# CrackberryPi_1_0_6_2_random.net
KiCad netlist of a schematic drawn in EAGLE
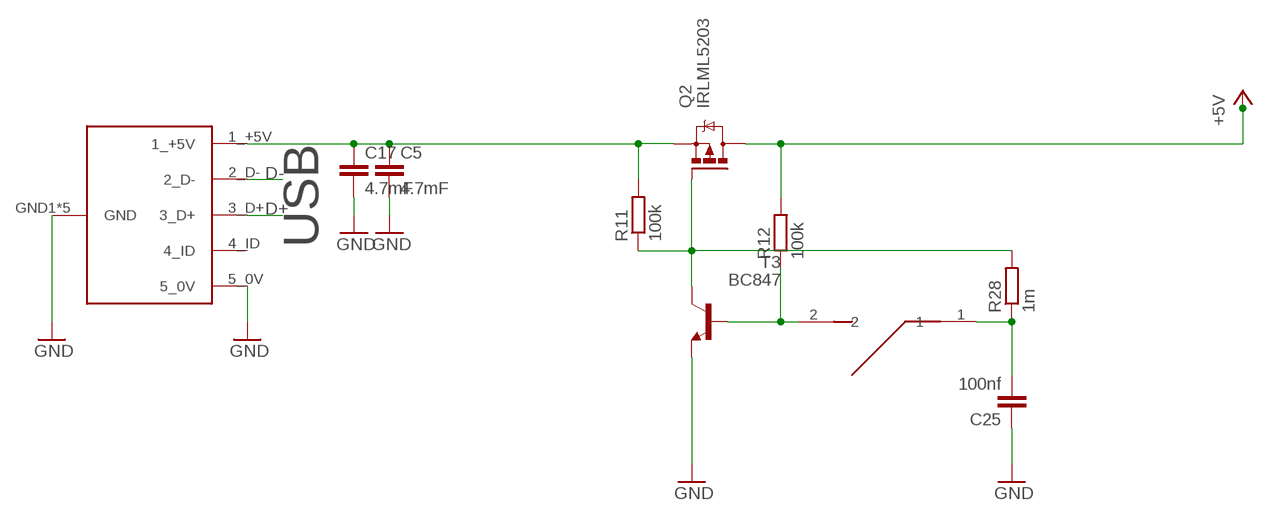
[diagram p0: schematic, sheet 1, part 1 of 2]
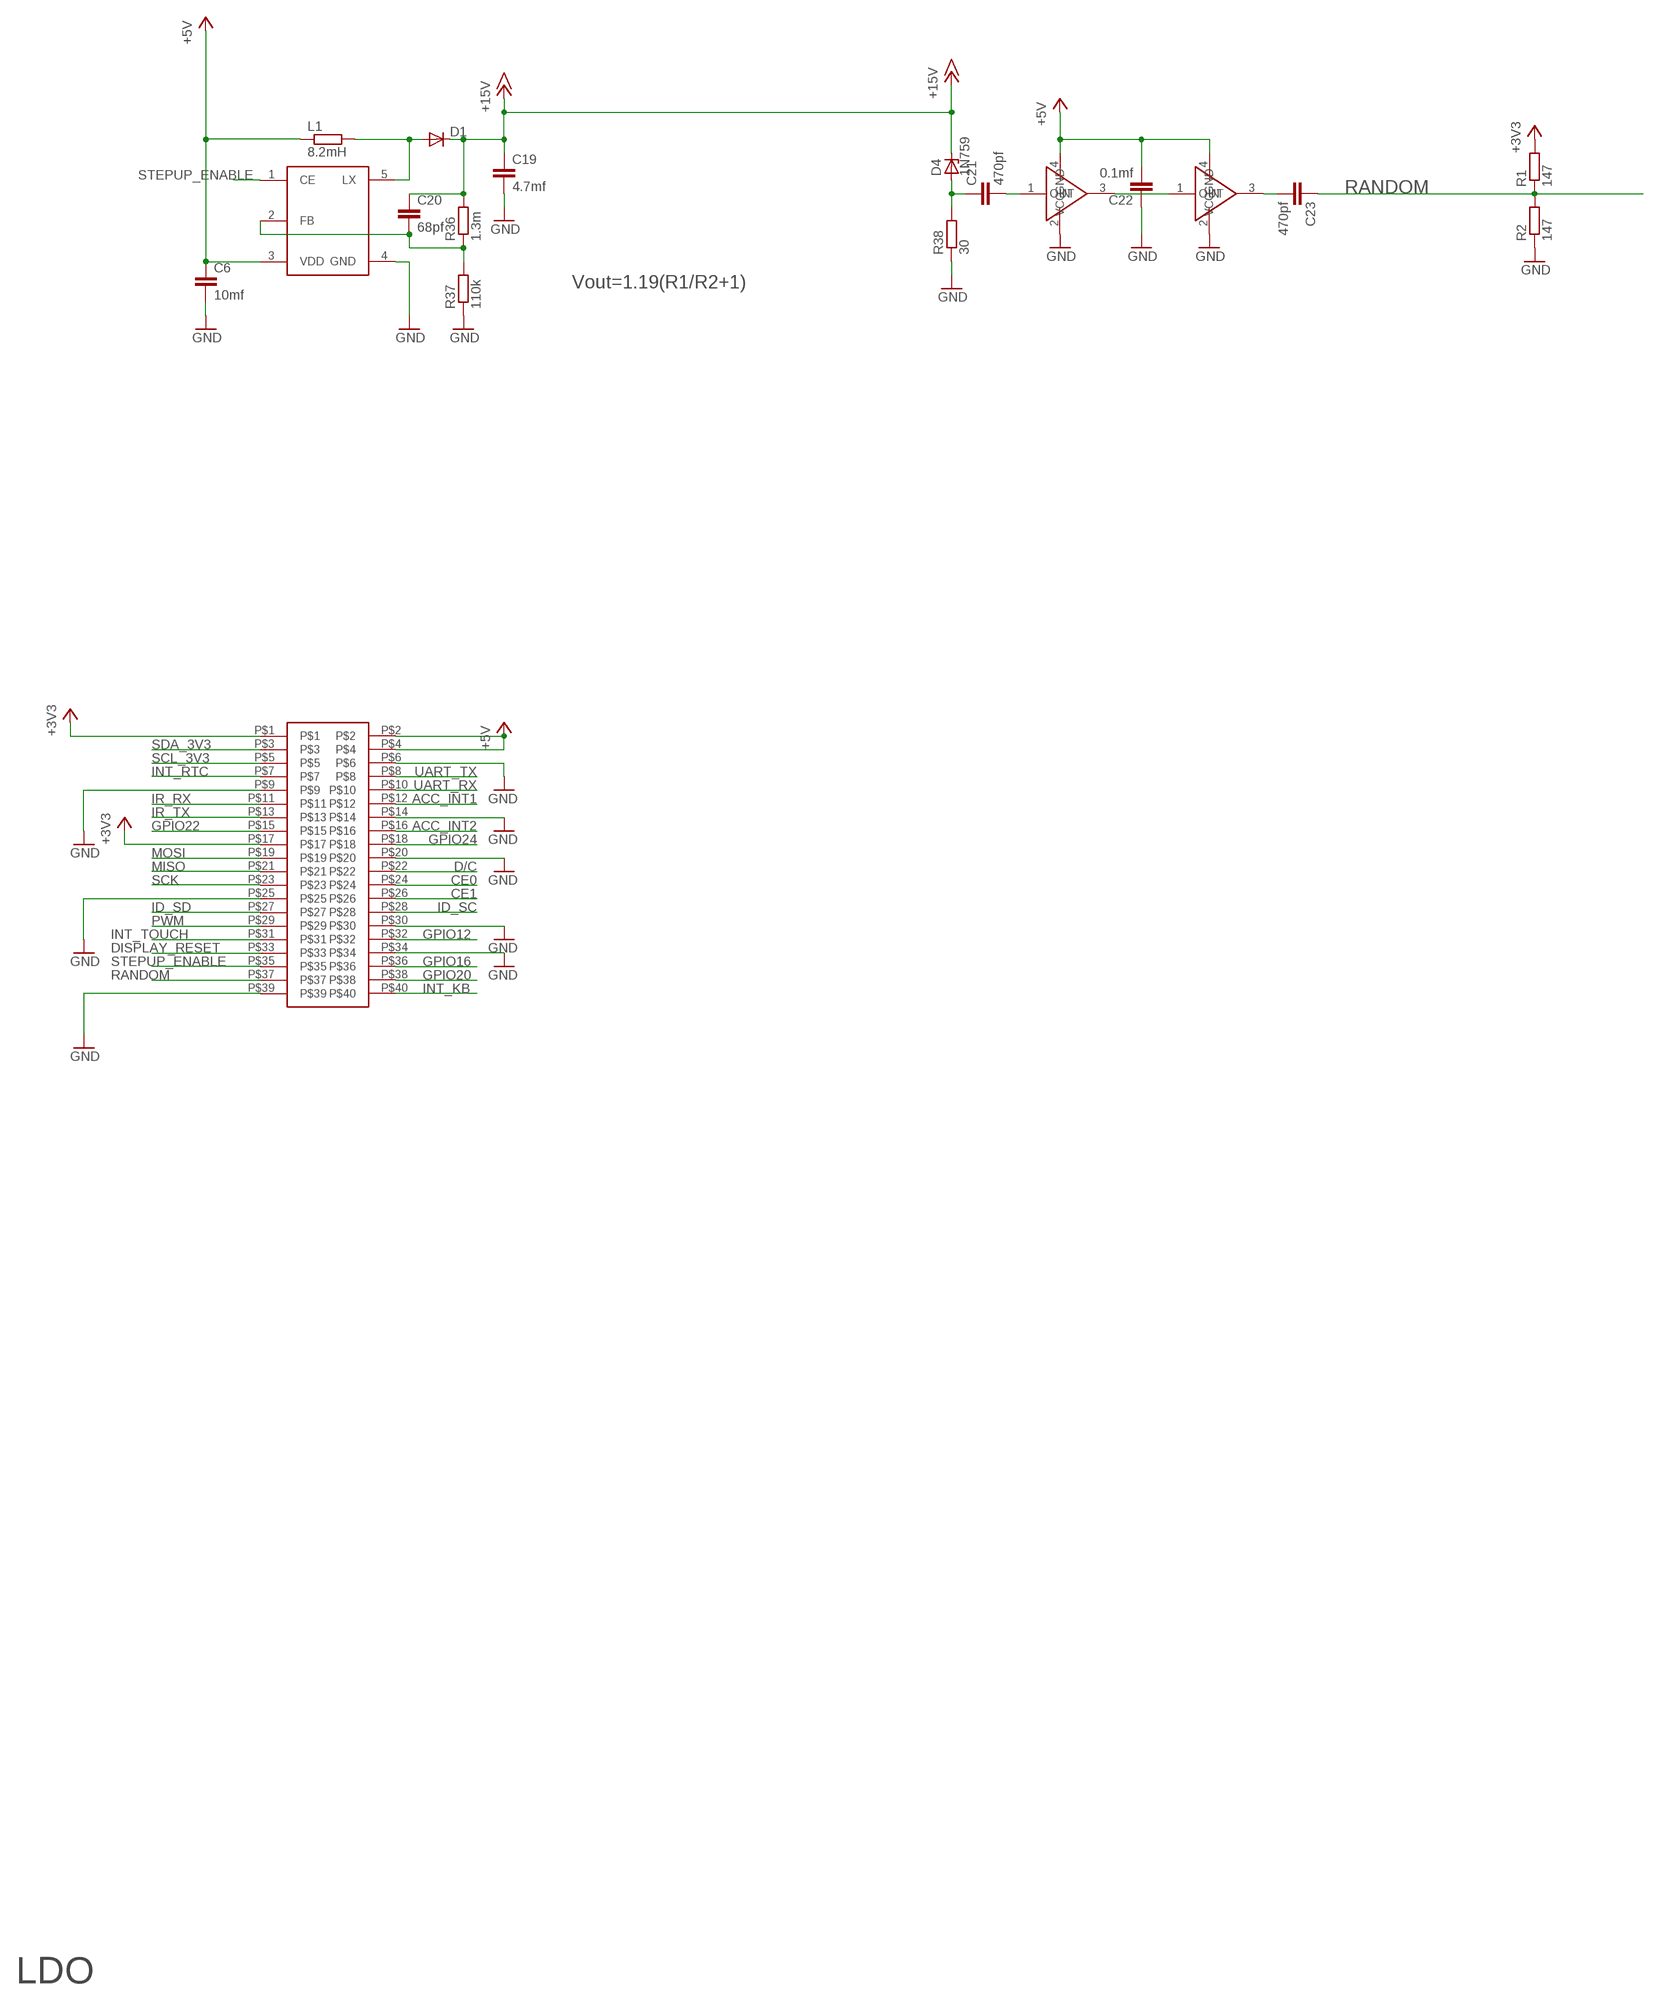
[diagram p1: schematic, sheet 1, part 2 of 2]

(export (version "E")
  (design (tool "Eeschema 10.0.6"))
  (components
    (comp (ref "C5")
      (value "4.7mF")
      (footprint "eagle-import:C0603")
      (libsource (lib "eagle-import") (part "C-EUC0603"))
    )
    (comp (ref "C6")
      (value "10mf")
      (footprint "eagle-import:C0603")
      (libsource (lib "eagle-import") (part "C-EUC0603"))
    )
    (comp (ref "C17")
      (value "4.7mF")
      (footprint "eagle-import:C0603")
      (libsource (lib "eagle-import") (part "C-EUC0603"))
    )
    (comp (ref "C19")
      (value "4.7mf")
      (footprint "eagle-import:C0603")
      (libsource (lib "eagle-import") (part "C-EUC0603"))
    )
    (comp (ref "C20")
      (value "68pf")
      (footprint "eagle-import:C0603")
      (libsource (lib "eagle-import") (part "C-EUC0603"))
    )
    (comp (ref "C21")
      (value "470pf")
      (footprint "eagle-import:C0603")
      (libsource (lib "eagle-import") (part "C-EUC0603"))
    )
    (comp (ref "C22")
      (value "0.1mf")
      (footprint "eagle-import:C0603")
      (libsource (lib "eagle-import") (part "C-EUC0603"))
    )
    (comp (ref "C23")
      (value "470pf")
      (footprint "eagle-import:C0603")
      (libsource (lib "eagle-import") (part "C-EUC0603"))
    )
    (comp (ref "C25")
      (value "100nf")
      (footprint "eagle-import:C0603")
      (libsource (lib "eagle-import") (part "C-EUC0603"))
    )
    (comp (ref "D1")
      (value "DIODE-SOD123")
      (footprint "eagle-import:SOD123")
      (libsource (lib "eagle-import") (part "DIODE-SOD123"))
    )
    (comp (ref "D4")
      (value "1N759")
      (footprint "eagle-import:SOD80C")
      (libsource (lib "eagle-import") (part "ZENER-DIODESOD80C"))
    )
    (comp (ref "L1")
      (value "8.2mH")
      (footprint "eagle-import:R1210")
      (libsource (lib "eagle-import") (part "R-EU_R1210"))
    )
    (comp (ref "Q2")
      (value "IRLML5203")
      (footprint "eagle-import:MICRO3")
      (libsource (lib "eagle-import") (part "IRLML5203"))
    )
    (comp (ref "R1")
      (value "147")
      (footprint "eagle-import:R0603")
      (libsource (lib "eagle-import") (part "R-EU_R0603"))
    )
    (comp (ref "R2")
      (value "147")
      (footprint "eagle-import:R0603")
      (libsource (lib "eagle-import") (part "R-EU_R0603"))
    )
    (comp (ref "R11")
      (value "100k")
      (footprint "eagle-import:R0603")
      (libsource (lib "eagle-import") (part "R-EU_R0603"))
    )
    (comp (ref "R12")
      (value "100k")
      (footprint "eagle-import:R0603")
      (libsource (lib "eagle-import") (part "R-EU_R0603"))
    )
    (comp (ref "R28")
      (value "1m")
      (footprint "eagle-import:R0603")
      (libsource (lib "eagle-import") (part "R-EU_R0603"))
    )
    (comp (ref "R36")
      (value "1.3m")
      (footprint "eagle-import:R0603")
      (libsource (lib "eagle-import") (part "R-EU_R0603"))
    )
    (comp (ref "R37")
      (value "110k")
      (footprint "eagle-import:R0603")
      (libsource (lib "eagle-import") (part "R-EU_R0603"))
    )
    (comp (ref "R38")
      (value "30")
      (footprint "eagle-import:R0603")
      (libsource (lib "eagle-import") (part "R-EU_R0603"))
    )
    (comp (ref "T3")
      (value "BC847")
      (footprint "eagle-import:SOT23")
      (libsource (lib "eagle-import") (part "BC847"))
    )
    (comp (ref "U$2")
      (value "NCP1406")
      (footprint "eagle-import:SOT23-5L")
      (libsource (lib "eagle-import") (part "NCP1406"))
    )
    (comp (ref "U$3")
      (value "MAX2650")
      (footprint "eagle-import:SOT143-W")
      (libsource (lib "eagle-import") (part "MAX2650"))
    )
    (comp (ref "U$8")
      (value "MOMSWITCH")
      (footprint "eagle-import:MOMSWITCH")
      (libsource (lib "eagle-import") (part "MOMSWITCH"))
    )
    (comp (ref "U$9")
      (value "MICRO_USB")
      (footprint "eagle-import:MICRO_USB")
      (libsource (lib "eagle-import") (part "MICRO_USB"))
    )
    (comp (ref "U$10")
      (value "MAX2650")
      (footprint "eagle-import:SOT143-W")
      (libsource (lib "eagle-import") (part "MAX2650"))
    )
    (comp (ref "U$11")
      (value "HEADER")
      (footprint "eagle-import:20X2")
      (libsource (lib "eagle-import") (part "HEADER"))
    )
  )
  (nets
    (net (code "1") (name "+3V3") (class "Default")
      (node (ref "R1") (pin "2") (pinfunction "2_2") (pintype "passive"))
      (node (ref "U$11") (pin "P$1") (pinfunction "P$1_P$1") (pintype "bidirectional"))
      (node (ref "U$11") (pin "P$17") (pinfunction "P$17_P$17") (pintype "bidirectional"))
    )
    (net (code "2") (name "+5V") (class "Default")
      (node (ref "C22") (pin "2") (pinfunction "2_2") (pintype "passive"))
      (node (ref "C6") (pin "1") (pinfunction "1_1") (pintype "passive"))
      (node (ref "L1") (pin "1") (pinfunction "1_1") (pintype "passive"))
      (node (ref "Q2") (pin "3") (pinfunction "D_3") (pintype "passive"))
      (node (ref "R12") (pin "2") (pinfunction "2_2") (pintype "passive"))
      (node (ref "U$10") (pin "4") (pinfunction "VCC_4") (pintype "bidirectional"))
      (node (ref "U$11") (pin "P$2") (pinfunction "P$2_P$2") (pintype "bidirectional"))
      (node (ref "U$11") (pin "P$4") (pinfunction "P$4_P$4") (pintype "bidirectional"))
      (node (ref "U$2") (pin "3") (pinfunction "VDD_3") (pintype "bidirectional"))
      (node (ref "U$3") (pin "4") (pinfunction "VCC_4") (pintype "bidirectional"))
    )
    (net (code "3") (name "+15V") (class "Default")
      (node (ref "C19") (pin "1") (pinfunction "1_1") (pintype "passive"))
      (node (ref "C20") (pin "1") (pinfunction "1_1") (pintype "passive"))
      (node (ref "D1") (pin "C") (pinfunction "C_C") (pintype "passive"))
      (node (ref "D4") (pin "C") (pinfunction "C_C") (pintype "passive"))
      (node (ref "R36") (pin "2") (pinfunction "2_2") (pintype "passive"))
    )
    (net (code "4") (name "/ACC_INT1") (class "Default")
      (node (ref "U$11") (pin "P$12") (pinfunction "P$12_P$12") (pintype "bidirectional"))
    )
    (net (code "5") (name "/ACC_INT2") (class "Default")
      (node (ref "U$11") (pin "P$16") (pinfunction "P$16_P$16") (pintype "bidirectional"))
    )
    (net (code "6") (name "/CE0") (class "Default")
      (node (ref "U$11") (pin "P$24") (pinfunction "P$24_P$24") (pintype "bidirectional"))
    )
    (net (code "7") (name "/CE1") (class "Default")
      (node (ref "U$11") (pin "P$26") (pinfunction "P$26_P$26") (pintype "bidirectional"))
    )
    (net (code "8") (name "/D+") (class "Default")
      (node (ref "U$9") (pin "3_D+") (pinfunction "3_D+_3_D+") (pintype "bidirectional"))
    )
    (net (code "9") (name "/D-") (class "Default")
      (node (ref "U$9") (pin "2_D-") (pinfunction "2_D-_2_D-") (pintype "bidirectional"))
    )
    (net (code "10") (name "/DISPLAY_RESET") (class "Default")
      (node (ref "U$11") (pin "P$33") (pinfunction "P$33_P$33") (pintype "bidirectional"))
    )
    (net (code "11") (name "/D{slash}C") (class "Default")
      (node (ref "U$11") (pin "P$22") (pinfunction "P$22_P$22") (pintype "bidirectional"))
    )
    (net (code "12") (name "/GPIO12") (class "Default")
      (node (ref "U$11") (pin "P$32") (pinfunction "P$32_P$32") (pintype "bidirectional"))
    )
    (net (code "13") (name "/GPIO16") (class "Default")
      (node (ref "U$11") (pin "P$36") (pinfunction "P$36_P$36") (pintype "bidirectional"))
    )
    (net (code "14") (name "/GPIO20") (class "Default")
      (node (ref "U$11") (pin "P$38") (pinfunction "P$38_P$38") (pintype "bidirectional"))
    )
    (net (code "15") (name "/GPIO22") (class "Default")
      (node (ref "U$11") (pin "P$15") (pinfunction "P$15_P$15") (pintype "bidirectional"))
    )
    (net (code "16") (name "/GPIO24") (class "Default")
      (node (ref "U$11") (pin "P$18") (pinfunction "P$18_P$18") (pintype "bidirectional"))
    )
    (net (code "17") (name "/ID_SC") (class "Default")
      (node (ref "U$11") (pin "P$28") (pinfunction "P$28_P$28") (pintype "bidirectional"))
    )
    (net (code "18") (name "/ID_SD") (class "Default")
      (node (ref "U$11") (pin "P$27") (pinfunction "P$27_P$27") (pintype "bidirectional"))
    )
    (net (code "19") (name "/INT_KB") (class "Default")
      (node (ref "U$11") (pin "P$40") (pinfunction "P$40_P$40") (pintype "bidirectional"))
    )
    (net (code "20") (name "/INT_RTC") (class "Default")
      (node (ref "U$11") (pin "P$7") (pinfunction "P$7_P$7") (pintype "bidirectional"))
    )
    (net (code "21") (name "/INT_TOUCH") (class "Default")
      (node (ref "U$11") (pin "P$31") (pinfunction "P$31_P$31") (pintype "bidirectional"))
    )
    (net (code "22") (name "/IR_RX") (class "Default")
      (node (ref "U$11") (pin "P$11") (pinfunction "P$11_P$11") (pintype "bidirectional"))
    )
    (net (code "23") (name "/IR_TX") (class "Default")
      (node (ref "U$11") (pin "P$13") (pinfunction "P$13_P$13") (pintype "bidirectional"))
    )
    (net (code "24") (name "/MISO") (class "Default")
      (node (ref "U$11") (pin "P$21") (pinfunction "P$21_P$21") (pintype "bidirectional"))
    )
    (net (code "25") (name "/MOSI") (class "Default")
      (node (ref "U$11") (pin "P$19") (pinfunction "P$19_P$19") (pintype "bidirectional"))
    )
    (net (code "26") (name "/PWM") (class "Default")
      (node (ref "U$11") (pin "P$29") (pinfunction "P$29_P$29") (pintype "bidirectional"))
    )
    (net (code "27") (name "/RANDOM") (class "Default")
      (node (ref "C23") (pin "1") (pinfunction "1_1") (pintype "passive"))
      (node (ref "R1") (pin "1") (pinfunction "1_1") (pintype "passive"))
      (node (ref "R2") (pin "2") (pinfunction "2_2") (pintype "passive"))
      (node (ref "U$11") (pin "P$37") (pinfunction "P$37_P$37") (pintype "bidirectional"))
    )
    (net (code "28") (name "/SCK") (class "Default")
      (node (ref "U$11") (pin "P$23") (pinfunction "P$23_P$23") (pintype "bidirectional"))
    )
    (net (code "29") (name "/SCL_3V3") (class "Default")
      (node (ref "U$11") (pin "P$5") (pinfunction "P$5_P$5") (pintype "bidirectional"))
    )
    (net (code "30") (name "/SDA_3V3") (class "Default")
      (node (ref "U$11") (pin "P$3") (pinfunction "P$3_P$3") (pintype "bidirectional"))
    )
    (net (code "31") (name "/STEPUP_ENABLE") (class "Default")
      (node (ref "U$11") (pin "P$35") (pinfunction "P$35_P$35") (pintype "bidirectional"))
      (node (ref "U$2") (pin "1") (pinfunction "CE_1") (pintype "bidirectional"))
    )
    (net (code "32") (name "/UART_RX") (class "Default")
      (node (ref "U$11") (pin "P$10") (pinfunction "P$10_P$10") (pintype "bidirectional"))
    )
    (net (code "33") (name "/UART_TX") (class "Default")
      (node (ref "U$11") (pin "P$8") (pinfunction "P$8_P$8") (pintype "bidirectional"))
    )
    (net (code "34") (name "GND") (class "Default")
      (node (ref "C17") (pin "2") (pinfunction "2_2") (pintype "passive"))
      (node (ref "C19") (pin "2") (pinfunction "2_2") (pintype "passive"))
      (node (ref "C22") (pin "1") (pinfunction "1_1") (pintype "passive"))
      (node (ref "C25") (pin "1") (pinfunction "1_1") (pintype "passive"))
      (node (ref "C5") (pin "2") (pinfunction "2_2") (pintype "passive"))
      (node (ref "C6") (pin "2") (pinfunction "2_2") (pintype "passive"))
      (node (ref "R2") (pin "1") (pinfunction "1_1") (pintype "passive"))
      (node (ref "R37") (pin "1") (pinfunction "1_1") (pintype "passive"))
      (node (ref "R38") (pin "1") (pinfunction "1_1") (pintype "passive"))
      (node (ref "T3") (pin "2") (pinfunction "E_2") (pintype "passive"))
      (node (ref "U$10") (pin "2") (pinfunction "GND_2") (pintype "bidirectional"))
      (node (ref "U$11") (pin "P$14") (pinfunction "P$14_P$14") (pintype "bidirectional"))
      (node (ref "U$11") (pin "P$20") (pinfunction "P$20_P$20") (pintype "bidirectional"))
      (node (ref "U$11") (pin "P$25") (pinfunction "P$25_P$25") (pintype "bidirectional"))
      (node (ref "U$11") (pin "P$30") (pinfunction "P$30_P$30") (pintype "bidirectional"))
      (node (ref "U$11") (pin "P$34") (pinfunction "P$34_P$34") (pintype "bidirectional"))
      (node (ref "U$11") (pin "P$39") (pinfunction "P$39_P$39") (pintype "bidirectional"))
      (node (ref "U$11") (pin "P$6") (pinfunction "P$6_P$6") (pintype "bidirectional"))
      (node (ref "U$11") (pin "P$9") (pinfunction "P$9_P$9") (pintype "bidirectional"))
      (node (ref "U$2") (pin "4") (pinfunction "GND_4") (pintype "bidirectional"))
      (node (ref "U$3") (pin "2") (pinfunction "GND_2") (pintype "bidirectional"))
      (node (ref "U$9") (pin "5_0V") (pinfunction "5_0V_5_0V") (pintype "bidirectional"))
      (node (ref "U$9") (pin "GND1") (pinfunction "GND_GND1") (pintype "bidirectional"))
      (node (ref "U$9") (pin "GND2") (pinfunction "GND_GND2") (pintype "bidirectional"))
      (node (ref "U$9") (pin "GND5") (pinfunction "GND_GND5") (pintype "bidirectional"))
      (node (ref "U$9") (pin "P$1") (pinfunction "GND_P$1") (pintype "bidirectional"))
      (node (ref "U$9") (pin "P$7") (pinfunction "GND_P$7") (pintype "bidirectional"))
    )
    (net (code "35") (name "Net-(C21-Pad1)") (class "Default")
      (node (ref "C21") (pin "1") (pinfunction "1_1") (pintype "passive"))
      (node (ref "D4") (pin "A") (pinfunction "A_A") (pintype "passive"))
      (node (ref "R38") (pin "2") (pinfunction "2_2") (pintype "passive"))
    )
    (net (code "36") (name "Net-(C25-Pad2)") (class "Default")
      (node (ref "C25") (pin "2") (pinfunction "2_2") (pintype "passive"))
      (node (ref "R28") (pin "1") (pinfunction "1_1") (pintype "passive"))
      (node (ref "U$8") (pin "1") (pinfunction "1_1") (pintype "bidirectional"))
    )
    (net (code "37") (name "Net-(Q2-G)") (class "Default")
      (node (ref "Q2") (pin "1") (pinfunction "G_1") (pintype "passive"))
      (node (ref "R11") (pin "1") (pinfunction "1_1") (pintype "passive"))
      (node (ref "R28") (pin "2") (pinfunction "2_2") (pintype "passive"))
      (node (ref "T3") (pin "3") (pinfunction "C_3") (pintype "passive"))
    )
    (net (code "38") (name "Net-(Q2-S)") (class "Default")
      (node (ref "C17") (pin "1") (pinfunction "1_1") (pintype "passive"))
      (node (ref "C5") (pin "1") (pinfunction "1_1") (pintype "passive"))
      (node (ref "Q2") (pin "2") (pinfunction "S_2") (pintype "passive"))
      (node (ref "R11") (pin "2") (pinfunction "2_2") (pintype "passive"))
      (node (ref "U$9") (pin "1_+5V") (pinfunction "1_+5V_1_+5V") (pintype "bidirectional"))
    )
    (net (code "39") (name "Net-(T3-B)") (class "Default")
      (node (ref "R12") (pin "1") (pinfunction "1_1") (pintype "passive"))
      (node (ref "T3") (pin "1") (pinfunction "B_1") (pintype "passive"))
      (node (ref "U$8") (pin "2") (pinfunction "2_2") (pintype "bidirectional"))
    )
    (net (code "40") (name "Net-(U$2-FB)") (class "Default")
      (node (ref "C20") (pin "2") (pinfunction "2_2") (pintype "passive"))
      (node (ref "R36") (pin "1") (pinfunction "1_1") (pintype "passive"))
      (node (ref "R37") (pin "2") (pinfunction "2_2") (pintype "passive"))
      (node (ref "U$2") (pin "2") (pinfunction "FB_2") (pintype "bidirectional"))
    )
    (net (code "41") (name "Net-(U$2-LX)") (class "Default")
      (node (ref "D1") (pin "A") (pinfunction "A_A") (pintype "passive"))
      (node (ref "L1") (pin "2") (pinfunction "2_2") (pintype "passive"))
      (node (ref "U$2") (pin "5") (pinfunction "LX_5") (pintype "bidirectional"))
    )
    (net (code "42") (name "Net-(U$3-IN)") (class "Default")
      (node (ref "C21") (pin "2") (pinfunction "2_2") (pintype "passive"))
      (node (ref "U$3") (pin "1") (pinfunction "IN_1") (pintype "bidirectional"))
    )
    (net (code "43") (name "Net-(U$10-IN)") (class "Default")
      (node (ref "U$10") (pin "1") (pinfunction "IN_1") (pintype "bidirectional"))
      (node (ref "U$3") (pin "3") (pinfunction "OUT_3") (pintype "bidirectional"))
    )
    (net (code "44") (name "Net-(U$10-OUT)") (class "Default")
      (node (ref "C23") (pin "2") (pinfunction "2_2") (pintype "passive"))
      (node (ref "U$10") (pin "3") (pinfunction "OUT_3") (pintype "bidirectional"))
    )
    (net (code "45") (name "unconnected-(U$9-Pad4_ID)") (class "Default")
      (node (ref "U$9") (pin "4_ID") (pinfunction "4_ID_4_ID") (pintype "bidirectional"))
    )
  )
)
